# RainMeterRAK.net
KiCad netlist of a schematic drawn in EAGLE
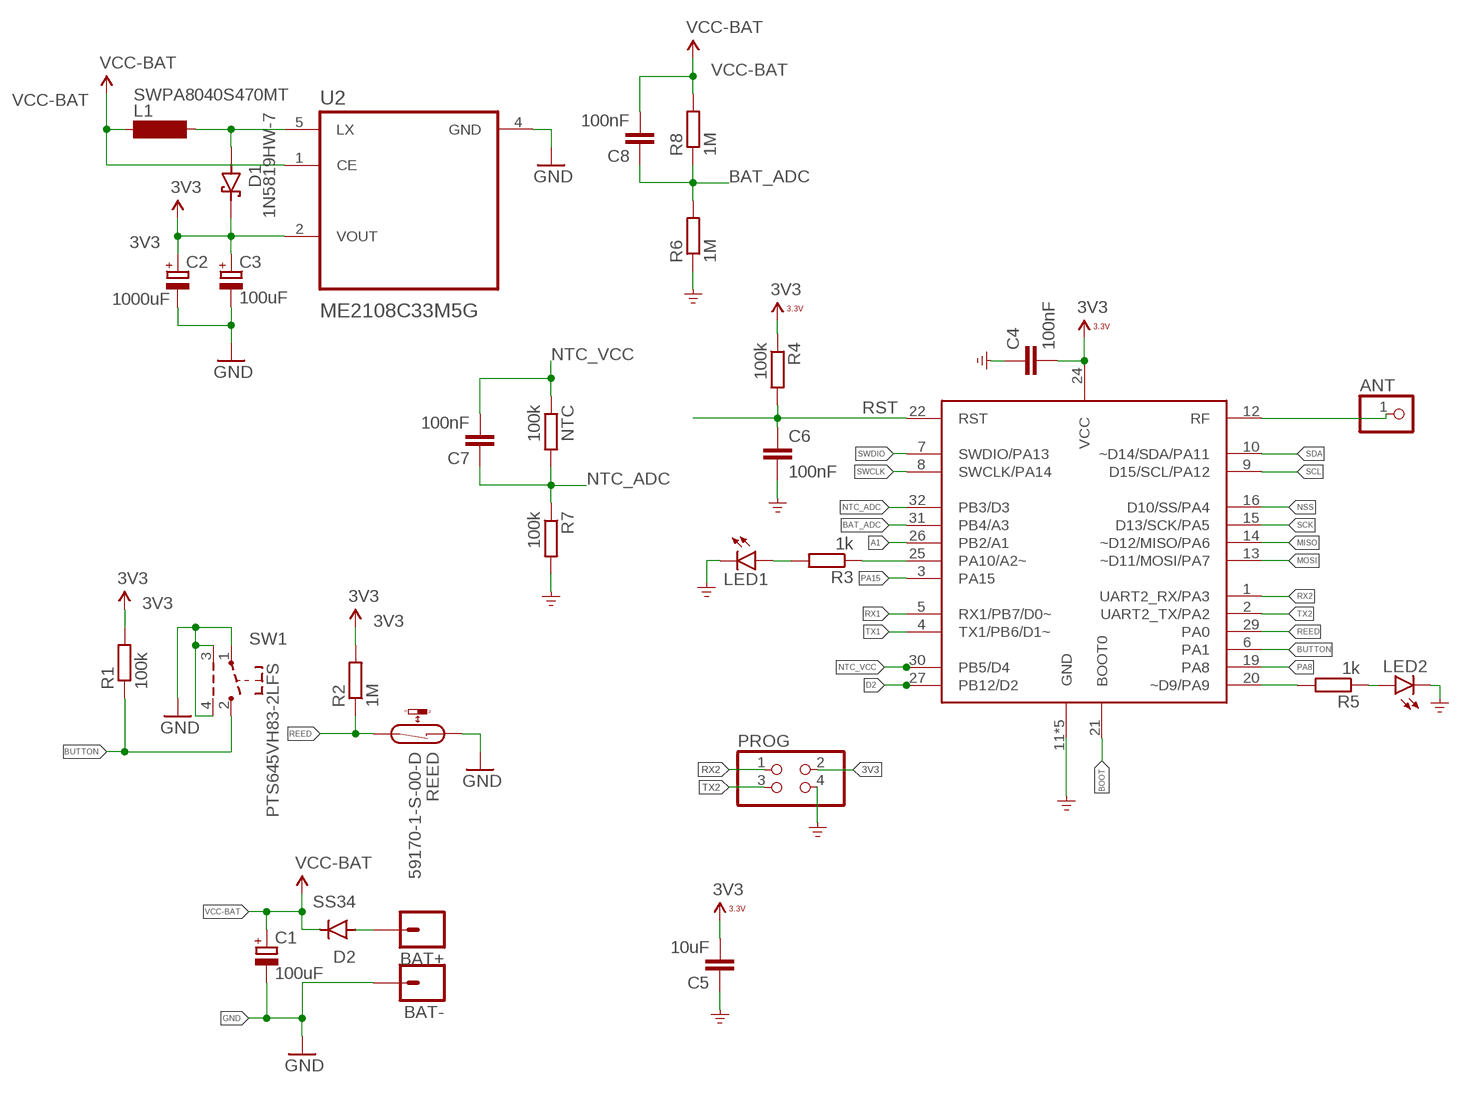
[diagram p0: schematic, sheet 1]

(export (version "E")
  (design (tool "Eeschema 10.0.6"))
  (components
    (comp (ref "ANT")
      (value "PINHD-1X1")
      (footprint "eagle-import:1X01")
      (libsource (lib "eagle-import") (part "PINHD-1X1"))
    )
    (comp (ref "BAT+")
      (value "M01OFFSET")
      (footprint "eagle-import:1X01_OFFSET")
      (libsource (lib "eagle-import") (part "M01OFFSET"))
    )
    (comp (ref "BAT-")
      (value "M01OFFSET")
      (footprint "eagle-import:1X01_OFFSET")
      (libsource (lib "eagle-import") (part "M01OFFSET"))
    )
    (comp (ref "C1")
      (value "100uF")
      (footprint "eagle-import:CT3528")
      (libsource (lib "eagle-import") (part "CPOL-EUCT3528"))
    )
    (comp (ref "C2")
      (value "1000uF")
      (footprint "eagle-import:140CLH-0810")
      (libsource (lib "eagle-import") (part "CPOL-EU140CLH-0810"))
    )
    (comp (ref "C3")
      (value "100uF")
      (footprint "eagle-import:CT3528")
      (libsource (lib "eagle-import") (part "CPOL-EUCT3528"))
    )
    (comp (ref "C4")
      (value "100nF")
      (footprint "eagle-import:C0603")
      (libsource (lib "eagle-import") (part "C-EUC0603"))
    )
    (comp (ref "C5")
      (value "10uF")
      (footprint "eagle-import:C0603")
      (libsource (lib "eagle-import") (part "C-EUC0603"))
    )
    (comp (ref "C6")
      (value "100nF")
      (footprint "eagle-import:C0603")
      (libsource (lib "eagle-import") (part "C-EUC0603"))
    )
    (comp (ref "C7")
      (value "100nF")
      (footprint "eagle-import:C0603")
      (libsource (lib "eagle-import") (part "C-EUC0603"))
    )
    (comp (ref "C8")
      (value "100nF")
      (footprint "eagle-import:C0603")
      (libsource (lib "eagle-import") (part "C-EUC0603"))
    )
    (comp (ref "D1")
      (value "1N5819HW-7")
      (footprint "eagle-import:SOD3715X145N")
      (fields (field (name "MF") "Diodes Inc."))
      (libsource (lib "eagle-import") (part "1N5819HW-7"))
    )
    (comp (ref "D2")
      (value "SS34")
      (footprint "eagle-import:SOD-123_MINI-SMA")
      (libsource (lib "eagle-import") (part "CGRM400-G1"))
    )
    (comp (ref "L1")
      (value "SWPA8040S470MT")
      (footprint "eagle-import:SWPA8040S")
      (libsource (lib "eagle-import") (part "SWPA8040S"))
    )
    (comp (ref "LED1")
      (value "LEDCHIP-LED0603")
      (footprint "eagle-import:CHIP-LED0603")
      (libsource (lib "eagle-import") (part "LEDCHIP-LED0603"))
    )
    (comp (ref "LED2")
      (value "LEDCHIP-LED0603")
      (footprint "eagle-import:CHIP-LED0603")
      (libsource (lib "eagle-import") (part "LEDCHIP-LED0603"))
    )
    (comp (ref "NTC")
      (value "100k")
      (footprint "eagle-import:R0603")
      (libsource (lib "eagle-import") (part "R-EU_R0603"))
    )
    (comp (ref "PROG")
      (value "PINHD-2X2")
      (footprint "eagle-import:2X02")
      (libsource (lib "eagle-import") (part "PINHD-2X2"))
    )
    (comp (ref "R1")
      (value "100k")
      (footprint "eagle-import:R0603")
      (libsource (lib "eagle-import") (part "R-EU_R0603"))
    )
    (comp (ref "R2")
      (value "1M")
      (footprint "eagle-import:R0603")
      (libsource (lib "eagle-import") (part "R-EU_R0603"))
    )
    (comp (ref "R3")
      (value "1k")
      (footprint "eagle-import:R0603")
      (libsource (lib "eagle-import") (part "R-EU_R0603"))
    )
    (comp (ref "R4")
      (value "100k")
      (footprint "eagle-import:R0603")
      (libsource (lib "eagle-import") (part "R-EU_R0603"))
    )
    (comp (ref "R5")
      (value "1k")
      (footprint "eagle-import:R0603")
      (libsource (lib "eagle-import") (part "R-EU_R0603"))
    )
    (comp (ref "R6")
      (value "1M")
      (footprint "eagle-import:R0603")
      (libsource (lib "eagle-import") (part "R-EU_R0603"))
    )
    (comp (ref "R7")
      (value "100k")
      (footprint "eagle-import:R0603")
      (libsource (lib "eagle-import") (part "R-EU_R0603"))
    )
    (comp (ref "R8")
      (value "1M")
      (footprint "eagle-import:R0603")
      (libsource (lib "eagle-import") (part "R-EU_R0603"))
    )
    (comp (ref "REED")
      (value "59170-1-S-00-D")
      (footprint "eagle-import:CT10-G1")
      (fields (field (name "MF") "COTO TECHNOLOGY") (field (name "MPN") "CT10-1530-G1"))
      (libsource (lib "eagle-import") (part "REED-SWITCH-CT10-1530-G1"))
    )
    (comp (ref "SW1")
      (value "PTS645VH83-2LFS")
      (footprint "eagle-import:SW_TACT_STANDARD_RIGHT_ANGLE")
      (libsource (lib "eagle-import") (part "SW_TACT_4P_B"))
    )
    (comp (ref "U1")
      (value "RAK3172HF")
      (footprint "eagle-import:RAK3172")
      (libsource (lib "eagle-import") (part "RAK3172HF"))
    )
    (comp (ref "U2")
      (value "ME2108C33M5G")
      (footprint "eagle-import:SOT23-5")
      (fields (field (name "MF") "Texas Instruments") (field (name "MP") "TLV62568DBVR"))
      (libsource (lib "eagle-import") (part "ME2108C33M5G"))
    )
  )
  (nets
    (net (code "1") (name "/RST") (class "Default")
      (node (ref "C6") (pin "1") (pinfunction "1_1") (pintype "passive"))
      (node (ref "R4") (pin "2") (pinfunction "2_2") (pintype "passive"))
      (node (ref "U1") (pin "22") (pinfunction "RST_22") (pintype "input"))
    )
    (net (code "2") (name "3V3") (class "Default")
      (node (ref "C2") (pin "+") (pinfunction "+_+") (pintype "passive"))
      (node (ref "C3") (pin "+") (pinfunction "+_+") (pintype "passive"))
      (node (ref "C4") (pin "2") (pinfunction "2_2") (pintype "passive"))
      (node (ref "C5") (pin "2") (pinfunction "2_2") (pintype "passive"))
      (node (ref "D1") (pin "C") (pinfunction "K_C") (pintype "passive"))
      (node (ref "PROG") (pin "2") (pinfunction "2_2") (pintype "passive"))
      (node (ref "R1") (pin "2") (pinfunction "2_2") (pintype "passive"))
      (node (ref "R2") (pin "2") (pinfunction "2_2") (pintype "passive"))
      (node (ref "R4") (pin "1") (pinfunction "1_1") (pintype "passive"))
      (node (ref "U1") (pin "24") (pinfunction "VCC_24") (pintype "power_in"))
      (node (ref "U2") (pin "2") (pinfunction "VOUT_2") (pintype "bidirectional"))
    )
    (net (code "3") (name "A1") (class "Default")
      (node (ref "U1") (pin "26") (pinfunction "PB2/A1_26") (pintype "bidirectional"))
    )
    (net (code "4") (name "BAT_ADC") (class "Default")
      (node (ref "C8") (pin "1") (pinfunction "1_1") (pintype "passive"))
      (node (ref "R6") (pin "2") (pinfunction "2_2") (pintype "passive"))
      (node (ref "R8") (pin "1") (pinfunction "1_1") (pintype "passive"))
      (node (ref "U1") (pin "31") (pinfunction "PB4/A3_31") (pintype "bidirectional"))
    )
    (net (code "5") (name "BOOT") (class "Default")
      (node (ref "U1") (pin "21") (pinfunction "BOOT0_21") (pintype "input"))
    )
    (net (code "6") (name "BUTTON") (class "Default")
      (node (ref "R1") (pin "1") (pinfunction "1_1") (pintype "passive"))
      (node (ref "SW1") (pin "2") (pinfunction "2_2") (pintype "passive"))
      (node (ref "U1") (pin "6") (pinfunction "PA1_6") (pintype "bidirectional"))
    )
    (net (code "7") (name "D2") (class "Default")
      (node (ref "U1") (pin "27") (pinfunction "PB12/D2_27") (pintype "bidirectional"))
    )
    (net (code "8") (name "GND") (class "Default")
      (node (ref "BAT-") (pin "1") (pinfunction "1_1") (pintype "passive"))
      (node (ref "C1") (pin "-") (pinfunction "-_-") (pintype "passive"))
      (node (ref "C2") (pin "-") (pinfunction "-_-") (pintype "passive"))
      (node (ref "C3") (pin "-") (pinfunction "-_-") (pintype "passive"))
      (node (ref "C4") (pin "1") (pinfunction "1_1") (pintype "passive"))
      (node (ref "C5") (pin "1") (pinfunction "1_1") (pintype "passive"))
      (node (ref "C6") (pin "2") (pinfunction "2_2") (pintype "passive"))
      (node (ref "LED1") (pin "C") (pinfunction "C_C") (pintype "passive"))
      (node (ref "LED2") (pin "C") (pinfunction "C_C") (pintype "passive"))
      (node (ref "PROG") (pin "4") (pinfunction "4_4") (pintype "passive"))
      (node (ref "R6") (pin "1") (pinfunction "1_1") (pintype "passive"))
      (node (ref "R7") (pin "2") (pinfunction "2_2") (pintype "passive"))
      (node (ref "REED") (pin "1") (pinfunction "1_1") (pintype "passive"))
      (node (ref "SW1") (pin "1") (pinfunction "1_1") (pintype "passive"))
      (node (ref "SW1") (pin "3") (pinfunction "3_3") (pintype "passive"))
      (node (ref "SW1") (pin "4") (pinfunction "4_4") (pintype "passive"))
      (node (ref "U1") (pin "11") (pinfunction "GND_11") (pintype "power_in"))
      (node (ref "U1") (pin "17") (pinfunction "GND_17") (pintype "power_in"))
      (node (ref "U1") (pin "18") (pinfunction "GND_18") (pintype "power_in"))
      (node (ref "U1") (pin "23") (pinfunction "GND_23") (pintype "power_in"))
      (node (ref "U1") (pin "28") (pinfunction "GND_28") (pintype "power_in"))
      (node (ref "U2") (pin "4") (pinfunction "GND_4") (pintype "power_in"))
    )
    (net (code "9") (name "MISO") (class "Default")
      (node (ref "U1") (pin "14") (pinfunction "~{D12/MISO/PA6}_14") (pintype "bidirectional"))
    )
    (net (code "10") (name "MOSI") (class "Default")
      (node (ref "U1") (pin "13") (pinfunction "~{D11/MOSI/PA7}_13") (pintype "bidirectional"))
    )
    (net (code "11") (name "NSS") (class "Default")
      (node (ref "U1") (pin "16") (pinfunction "D10/SS/PA4_16") (pintype "bidirectional"))
    )
    (net (code "12") (name "NTC_ADC") (class "Default")
      (node (ref "C7") (pin "1") (pinfunction "1_1") (pintype "passive"))
      (node (ref "NTC") (pin "2") (pinfunction "2_2") (pintype "passive"))
      (node (ref "R7") (pin "1") (pinfunction "1_1") (pintype "passive"))
      (node (ref "U1") (pin "32") (pinfunction "PB3/D3_32") (pintype "bidirectional"))
    )
    (net (code "13") (name "NTC_VCC") (class "Default")
      (node (ref "C7") (pin "2") (pinfunction "2_2") (pintype "passive"))
      (node (ref "NTC") (pin "1") (pinfunction "1_1") (pintype "passive"))
      (node (ref "U1") (pin "30") (pinfunction "PB5/D4_30") (pintype "bidirectional"))
    )
    (net (code "14") (name "Net-(BAT+-Pad1)") (class "Default")
      (node (ref "BAT+") (pin "1") (pinfunction "1_1") (pintype "passive"))
      (node (ref "D2") (pin "A") (pinfunction "A_A") (pintype "passive"))
    )
    (net (code "15") (name "Net-(LED1-PadA)") (class "Default")
      (node (ref "LED1") (pin "A") (pinfunction "A_A") (pintype "passive"))
      (node (ref "R3") (pin "2") (pinfunction "2_2") (pintype "passive"))
    )
    (net (code "16") (name "Net-(LED2-PadA)") (class "Default")
      (node (ref "LED2") (pin "A") (pinfunction "A_A") (pintype "passive"))
      (node (ref "R5") (pin "1") (pinfunction "1_1") (pintype "passive"))
    )
    (net (code "17") (name "Net-(U1-PA10{slash}A2~{})") (class "Default")
      (node (ref "R3") (pin "1") (pinfunction "1_1") (pintype "passive"))
      (node (ref "U1") (pin "25") (pinfunction "PA10/A2~{}_25") (pintype "bidirectional"))
    )
    (net (code "18") (name "Net-(U1-RF)") (class "Default")
      (node (ref "ANT") (pin "1") (pinfunction "1_1") (pintype "passive"))
      (node (ref "U1") (pin "12") (pinfunction "RF_12") (pintype "output"))
    )
    (net (code "19") (name "Net-(U1-~{D9{slash}PA9})") (class "Default")
      (node (ref "R5") (pin "2") (pinfunction "2_2") (pintype "passive"))
      (node (ref "U1") (pin "20") (pinfunction "~{D9/PA9}_20") (pintype "bidirectional"))
    )
    (net (code "20") (name "Net-(U2-LX)") (class "Default")
      (node (ref "D1") (pin "A") (pinfunction "A_A") (pintype "passive"))
      (node (ref "L1") (pin "2") (pinfunction "2_2") (pintype "passive"))
      (node (ref "U2") (pin "5") (pinfunction "LX_5") (pintype "input"))
    )
    (net (code "21") (name "PA8") (class "Default")
      (node (ref "U1") (pin "19") (pinfunction "PA8_19") (pintype "bidirectional"))
    )
    (net (code "22") (name "PA15") (class "Default")
      (node (ref "U1") (pin "3") (pinfunction "PA15_3") (pintype "bidirectional"))
    )
    (net (code "23") (name "REED") (class "Default")
      (node (ref "R2") (pin "1") (pinfunction "1_1") (pintype "passive"))
      (node (ref "REED") (pin "2") (pinfunction "2_2") (pintype "passive"))
      (node (ref "U1") (pin "29") (pinfunction "PA0_29") (pintype "bidirectional"))
    )
    (net (code "24") (name "RX1") (class "Default")
      (node (ref "U1") (pin "5") (pinfunction "RX1/PB7/D0~{}_5") (pintype "bidirectional"))
    )
    (net (code "25") (name "RX2") (class "Default")
      (node (ref "PROG") (pin "1") (pinfunction "1_1") (pintype "passive"))
      (node (ref "U1") (pin "1") (pinfunction "UART2_RX/PA3_1") (pintype "bidirectional"))
    )
    (net (code "26") (name "SCK") (class "Default")
      (node (ref "U1") (pin "15") (pinfunction "D13/SCK/PA5_15") (pintype "bidirectional"))
    )
    (net (code "27") (name "SCL") (class "Default")
      (node (ref "U1") (pin "9") (pinfunction "D15/SCL/PA12_9") (pintype "bidirectional"))
    )
    (net (code "28") (name "SDA") (class "Default")
      (node (ref "U1") (pin "10") (pinfunction "~{D14/SDA/PA11}_10") (pintype "bidirectional"))
    )
    (net (code "29") (name "SWCLK") (class "Default")
      (node (ref "U1") (pin "8") (pinfunction "SWCLK/PA14_8") (pintype "bidirectional"))
    )
    (net (code "30") (name "SWDIO") (class "Default")
      (node (ref "U1") (pin "7") (pinfunction "SWDIO/PA13_7") (pintype "bidirectional"))
    )
    (net (code "31") (name "TX1") (class "Default")
      (node (ref "U1") (pin "4") (pinfunction "TX1/PB6/D1~{}_4") (pintype "bidirectional"))
    )
    (net (code "32") (name "TX2") (class "Default")
      (node (ref "PROG") (pin "3") (pinfunction "3_3") (pintype "passive"))
      (node (ref "U1") (pin "2") (pinfunction "UART2_TX/PA2_2") (pintype "bidirectional"))
    )
    (net (code "33") (name "VCC-BAT") (class "Default")
      (node (ref "C1") (pin "+") (pinfunction "+_+") (pintype "passive"))
      (node (ref "C8") (pin "2") (pinfunction "2_2") (pintype "passive"))
      (node (ref "D2") (pin "C") (pinfunction "C_C") (pintype "passive"))
      (node (ref "L1") (pin "1") (pinfunction "1_1") (pintype "passive"))
      (node (ref "R8") (pin "2") (pinfunction "2_2") (pintype "passive"))
      (node (ref "U2") (pin "1") (pinfunction "CE_1") (pintype "bidirectional"))
    )
  )
)
